# lampu_tidur_2.net
KiCad netlist of a schematic drawn in EAGLE
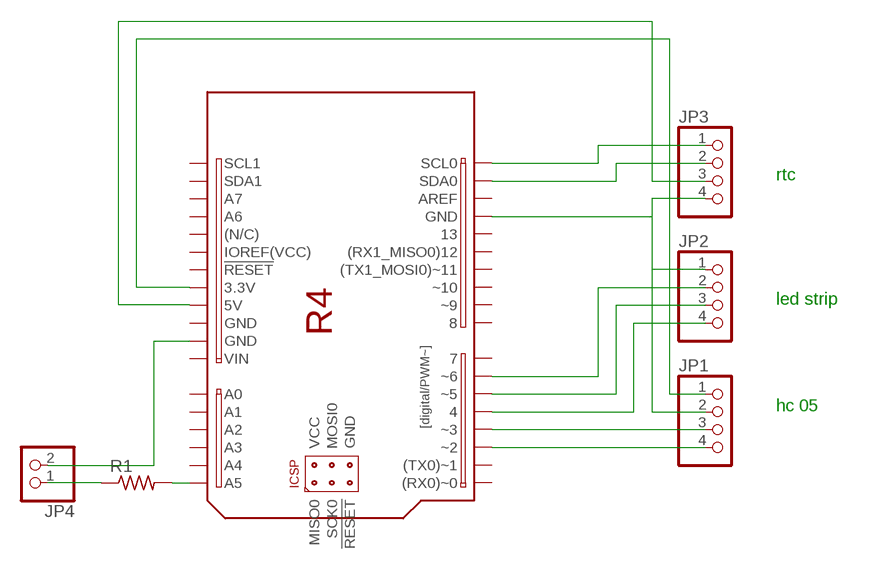
[diagram p0: schematic, sheet 1]

(export (version "E")
  (design (tool "Eeschema 10.0.6"))
  (components
    (comp (ref "JP1")
      (value "PINHD-1X4")
      (footprint "eagle-import:1X04")
      (libsource (lib "eagle-import") (part "PINHD-1X4"))
    )
    (comp (ref "JP2")
      (value "PINHD-1X4")
      (footprint "eagle-import:1X04")
      (libsource (lib "eagle-import") (part "PINHD-1X4"))
    )
    (comp (ref "JP3")
      (value "PINHD-1X4")
      (footprint "eagle-import:1X04")
      (libsource (lib "eagle-import") (part "PINHD-1X4"))
    )
    (comp (ref "JP4")
      (value "PINHD-1X2")
      (footprint "eagle-import:1X02")
      (libsource (lib "eagle-import") (part "PINHD-1X2"))
    )
    (comp (ref "PCB1")
      (value "R4-SHIELD")
      (footprint "eagle-import:R4-SHIELD")
      (libsource (lib "eagle-import") (part "R4-SHIELD"))
    )
    (comp (ref "R1")
      (value "R-US_0207/7")
      (footprint "eagle-import:0207_7")
      (libsource (lib "eagle-import") (part "R-US_0207/7"))
    )
  )
  (nets
    (net (code "1") (name "Net-(JP1-Pad1)") (class "Default")
      (node (ref "JP1") (pin "1") (pinfunction "1_1") (pintype "passive"))
      (node (ref "PCB1") (pin "3.3V") (pinfunction "3.3V_3.3V") (pintype "passive"))
    )
    (net (code "2") (name "Net-(JP1-Pad2)") (class "Default")
      (node (ref "JP1") (pin "2") (pinfunction "2_2") (pintype "passive"))
      (node (ref "JP2") (pin "1") (pinfunction "1_1") (pintype "passive"))
      (node (ref "JP3") (pin "4") (pinfunction "4_4") (pintype "passive"))
      (node (ref "PCB1") (pin "GND@3") (pinfunction "GND_GND@3") (pintype "passive"))
    )
    (net (code "3") (name "Net-(JP2-Pad4)") (class "Default")
      (node (ref "JP2") (pin "4") (pinfunction "4_4") (pintype "passive"))
      (node (ref "PCB1") (pin "4") (pinfunction "4_4") (pintype "passive"))
    )
    (net (code "4") (name "Net-(JP3-Pad3)") (class "Default")
      (node (ref "JP3") (pin "3") (pinfunction "3_3") (pintype "passive"))
      (node (ref "PCB1") (pin "5V") (pinfunction "5V_5V") (pintype "passive"))
    )
    (net (code "5") (name "Net-(JP4-Pad1)") (class "Default")
      (node (ref "JP4") (pin "1") (pinfunction "1_1") (pintype "passive"))
      (node (ref "R1") (pin "1") (pinfunction "1_1") (pintype "passive"))
    )
    (net (code "6") (name "Net-(JP4-Pad2)") (class "Default")
      (node (ref "JP4") (pin "2") (pinfunction "2_2") (pintype "passive"))
      (node (ref "PCB1") (pin "GND@1") (pinfunction "GND_GND@1") (pintype "passive"))
    )
    (net (code "7") (name "Net-(PCB1-PadA5)") (class "Default")
      (node (ref "PCB1") (pin "A5") (pinfunction "A5_A5") (pintype "passive"))
      (node (ref "R1") (pin "2") (pinfunction "2_2") (pintype "passive"))
    )
    (net (code "8") (name "Net-(PCB1-SCL0)") (class "Default")
      (node (ref "JP3") (pin "1") (pinfunction "1_1") (pintype "passive"))
      (node (ref "PCB1") (pin "SCL") (pinfunction "SCL0_SCL") (pintype "passive"))
    )
    (net (code "9") (name "Net-(PCB1-SDA0)") (class "Default")
      (node (ref "JP3") (pin "2") (pinfunction "2_2") (pintype "passive"))
      (node (ref "PCB1") (pin "SDA") (pinfunction "SDA0_SDA") (pintype "passive"))
    )
    (net (code "10") (name "Net-(PCB1-~{2})") (class "Default")
      (node (ref "JP1") (pin "4") (pinfunction "4_4") (pintype "passive"))
      (node (ref "PCB1") (pin "2") (pinfunction "~{2}_2") (pintype "passive"))
    )
    (net (code "11") (name "Net-(PCB1-~{3})") (class "Default")
      (node (ref "JP1") (pin "3") (pinfunction "3_3") (pintype "passive"))
      (node (ref "PCB1") (pin "3") (pinfunction "~{3}_3") (pintype "passive"))
    )
    (net (code "12") (name "Net-(PCB1-~{5})") (class "Default")
      (node (ref "JP2") (pin "3") (pinfunction "3_3") (pintype "passive"))
      (node (ref "PCB1") (pin "5") (pinfunction "~{5}_5") (pintype "passive"))
    )
    (net (code "13") (name "Net-(PCB1-~{6})") (class "Default")
      (node (ref "JP2") (pin "2") (pinfunction "2_2") (pintype "passive"))
      (node (ref "PCB1") (pin "6") (pinfunction "~{6}_6") (pintype "passive"))
    )
    (net (code "14") (name "unconnected-(PCB1-(N{slash}C)-PadN{slash}C)") (class "Default")
      (node (ref "PCB1") (pin "N/C") (pinfunction "(N/C)_N/C") (pintype "passive"))
    )
    (net (code "15") (name "unconnected-(PCB1-(RX0)~{0}-Pad0)") (class "Default")
      (node (ref "PCB1") (pin "0") (pinfunction "(RX0)~{0}_0") (pintype "passive"))
    )
    (net (code "16") (name "unconnected-(PCB1-(RX1_MISO0)12-Pad12)") (class "Default")
      (node (ref "PCB1") (pin "12") (pinfunction "(RX1_MISO0)12_12") (pintype "passive"))
    )
    (net (code "17") (name "unconnected-(PCB1-(TX0)~{1}-Pad1)") (class "Default")
      (node (ref "PCB1") (pin "1") (pinfunction "(TX0)~{1}_1") (pintype "passive"))
    )
    (net (code "18") (name "unconnected-(PCB1-(TX1_MOSI0)~{11}-Pad11)") (class "Default")
      (node (ref "PCB1") (pin "11") (pinfunction "(TX1_MOSI0)~{11}_11") (pintype "passive"))
    )
    (net (code "19") (name "unconnected-(PCB1-GND-PadGND@2)") (class "Default")
      (node (ref "PCB1") (pin "GND@2") (pinfunction "GND_GND@2") (pintype "passive"))
    )
    (net (code "20") (name "unconnected-(PCB1-GND-PadGND@4)") (class "Default")
      (node (ref "PCB1") (pin "GND@4") (pinfunction "GND_GND@4") (pintype "passive"))
    )
    (net (code "21") (name "unconnected-(PCB1-IOREF(VCC)-PadI{slash}OREF)") (class "Default")
      (node (ref "PCB1") (pin "I/OREF") (pinfunction "IOREF(VCC)_I/OREF") (pintype "passive"))
    )
    (net (code "22") (name "unconnected-(PCB1-MISO0-PadMISO)") (class "Default")
      (node (ref "PCB1") (pin "MISO") (pinfunction "MISO0_MISO") (pintype "passive"))
    )
    (net (code "23") (name "unconnected-(PCB1-MOSI0-PadMOSI)") (class "Default")
      (node (ref "PCB1") (pin "MOSI") (pinfunction "MOSI0_MOSI") (pintype "passive"))
    )
    (net (code "24") (name "unconnected-(PCB1-Pad7)") (class "Default")
      (node (ref "PCB1") (pin "7") (pinfunction "7_7") (pintype "passive"))
    )
    (net (code "25") (name "unconnected-(PCB1-Pad8)") (class "Default")
      (node (ref "PCB1") (pin "8") (pinfunction "8_8") (pintype "passive"))
    )
    (net (code "26") (name "unconnected-(PCB1-Pad13)") (class "Default")
      (node (ref "PCB1") (pin "13") (pinfunction "13_13") (pintype "passive"))
    )
    (net (code "27") (name "unconnected-(PCB1-PadA0)") (class "Default")
      (node (ref "PCB1") (pin "A0") (pinfunction "A0_A0") (pintype "passive"))
    )
    (net (code "28") (name "unconnected-(PCB1-PadA1)") (class "Default")
      (node (ref "PCB1") (pin "A1") (pinfunction "A1_A1") (pintype "passive"))
    )
    (net (code "29") (name "unconnected-(PCB1-PadA2)") (class "Default")
      (node (ref "PCB1") (pin "A2") (pinfunction "A2_A2") (pintype "passive"))
    )
    (net (code "30") (name "unconnected-(PCB1-PadA3)") (class "Default")
      (node (ref "PCB1") (pin "A3") (pinfunction "A3_A3") (pintype "passive"))
    )
    (net (code "31") (name "unconnected-(PCB1-PadA4)") (class "Default")
      (node (ref "PCB1") (pin "A4") (pinfunction "A4_A4") (pintype "passive"))
    )
    (net (code "32") (name "unconnected-(PCB1-PadA6)") (class "Default")
      (node (ref "PCB1") (pin "A6") (pinfunction "A6_A6") (pintype "passive"))
    )
    (net (code "33") (name "unconnected-(PCB1-PadA7)") (class "Default")
      (node (ref "PCB1") (pin "A7") (pinfunction "A7_A7") (pintype "passive"))
    )
    (net (code "34") (name "unconnected-(PCB1-PadAREF)") (class "Default")
      (node (ref "PCB1") (pin "AREF") (pinfunction "AREF_AREF") (pintype "passive"))
    )
    (net (code "35") (name "unconnected-(PCB1-PadSCL1)") (class "Default")
      (node (ref "PCB1") (pin "SCL1") (pinfunction "SCL1_SCL1") (pintype "passive"))
    )
    (net (code "36") (name "unconnected-(PCB1-PadSDA1)") (class "Default")
      (node (ref "PCB1") (pin "SDA1") (pinfunction "SDA1_SDA1") (pintype "passive"))
    )
    (net (code "37") (name "unconnected-(PCB1-PadVIN)") (class "Default")
      (node (ref "PCB1") (pin "VIN") (pinfunction "VIN_VIN") (pintype "passive"))
    )
    (net (code "38") (name "unconnected-(PCB1-SCK0-PadSCK)") (class "Default")
      (node (ref "PCB1") (pin "SCK") (pinfunction "SCK0_SCK") (pintype "passive"))
    )
    (net (code "39") (name "unconnected-(PCB1-VCC-Pad+5V)") (class "Default")
      (node (ref "PCB1") (pin "+5V") (pinfunction "VCC_+5V") (pintype "passive"))
    )
    (net (code "40") (name "unconnected-(PCB1-~{9}-Pad9)") (class "Default")
      (node (ref "PCB1") (pin "9") (pinfunction "~{9}_9") (pintype "passive"))
    )
    (net (code "41") (name "unconnected-(PCB1-~{10}-Pad10)") (class "Default")
      (node (ref "PCB1") (pin "10") (pinfunction "~{10}_10") (pintype "passive"))
    )
    (net (code "42") (name "unconnected-(PCB1-~{RESET}-Pad!RESET@1)") (class "Default")
      (node (ref "PCB1") (pin "!RESET@1") (pinfunction "~{RESET}_!RESET@1") (pintype "passive"))
    )
    (net (code "43") (name "unconnected-(PCB1-~{RESET}-Pad!RESET@2)") (class "Default")
      (node (ref "PCB1") (pin "!RESET@2") (pinfunction "~{RESET}_!RESET@2") (pintype "passive"))
    )
  )
)
